# Power_Supply.net
KiCad netlist of a schematic drawn in EAGLE
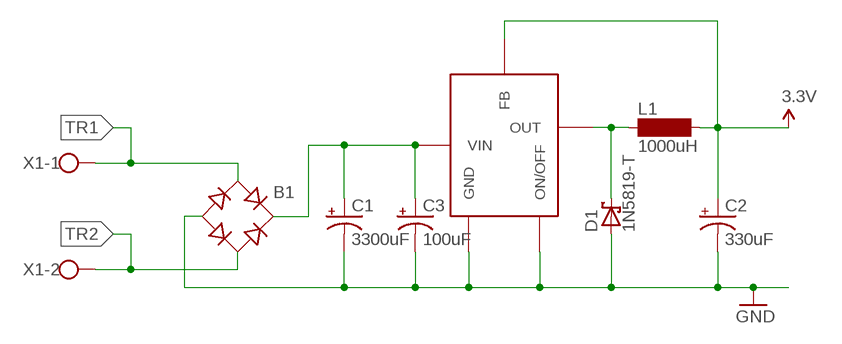
[diagram p0: schematic, sheet 1]

(export (version "E")
  (design (tool "Eeschema 10.0.6"))
  (components
    (comp (ref "B1")
      (value "DBDB101G")
      (footprint "eagle-import:DB")
      (libsource (lib "eagle-import") (part "DB?GDB101"))
    )
    (comp (ref "C1")
      (value "3300uF")
      (footprint "eagle-import:E7,5-18")
      (libsource (lib "eagle-import") (part "CPOL-USE7.5-18"))
    )
    (comp (ref "C2")
      (value "330uF")
      (footprint "eagle-import:E5-8,5")
      (libsource (lib "eagle-import") (part "CPOL-USE5-8.5"))
    )
    (comp (ref "C3")
      (value "100uF")
      (footprint "eagle-import:E5-8,5")
      (libsource (lib "eagle-import") (part "CPOL-USE5-8.5"))
    )
    (comp (ref "D1")
      (value "1N5819-T")
      (footprint "eagle-import:DO41-7.6")
      (libsource (lib "eagle-import") (part "1N5819-T"))
    )
    (comp (ref "L1")
      (value "1000uH")
      (footprint "eagle-import:BS11")
      (libsource (lib "eagle-import") (part "BS11"))
    )
    (comp (ref "U$1")
      (value "LM2575")
      (footprint "eagle-import:LINEAR-TECHNOLOGY_TO220-5")
      (libsource (lib "eagle-import") (part "LM2575"))
    )
    (comp (ref "X1")
      (value "W237-102")
      (footprint "eagle-import:W237-102")
      (fields (field (name "MPN") "237-102"))
      (libsource (lib "eagle-import") (part "W237-102"))
    )
  )
  (nets
    (net (code "1") (name "3.3V") (class "Default")
      (node (ref "C2") (pin "+") (pinfunction "+_+") (pintype "passive"))
      (node (ref "L1") (pin "2") (pinfunction "2_2") (pintype "passive"))
      (node (ref "U$1") (pin "FB") (pinfunction "FB_FB") (pintype "input"))
    )
    (net (code "2") (name "GND") (class "Default")
      (node (ref "B1") (pin "-") (pinfunction "-_-") (pintype "passive"))
      (node (ref "C1") (pin "-") (pinfunction "-_-") (pintype "passive"))
      (node (ref "C2") (pin "-") (pinfunction "-_-") (pintype "passive"))
      (node (ref "C3") (pin "-") (pinfunction "-_-") (pintype "passive"))
      (node (ref "D1") (pin "A") (pinfunction "A_A") (pintype "passive"))
      (node (ref "U$1") (pin "GND") (pinfunction "GND_GND") (pintype "power_in"))
      (node (ref "U$1") (pin "ON/OFF") (pinfunction "ON/OFF_ON/OFF") (pintype "input"))
    )
    (net (code "3") (name "Net-(B1-Pad+)") (class "Default")
      (node (ref "B1") (pin "+") (pinfunction "+_+") (pintype "passive"))
      (node (ref "C1") (pin "+") (pinfunction "+_+") (pintype "passive"))
      (node (ref "C3") (pin "+") (pinfunction "+_+") (pintype "passive"))
      (node (ref "U$1") (pin "VIN") (pinfunction "VIN_VIN") (pintype "power_in"))
    )
    (net (code "4") (name "Net-(D1-PadC)") (class "Default")
      (node (ref "D1") (pin "C") (pinfunction "C_C") (pintype "passive"))
      (node (ref "L1") (pin "1") (pinfunction "1_1") (pintype "passive"))
      (node (ref "U$1") (pin "OUT") (pinfunction "OUT_OUT") (pintype "power_in"))
    )
    (net (code "5") (name "TR1") (class "Default")
      (node (ref "B1") (pin "AC1") (pinfunction "AC1_AC1") (pintype "passive"))
      (node (ref "X1") (pin "1") (pinfunction "KL_1") (pintype "passive"))
    )
    (net (code "6") (name "TR2") (class "Default")
      (node (ref "B1") (pin "AC2") (pinfunction "AC2_AC2") (pintype "passive"))
      (node (ref "X1") (pin "2") (pinfunction "KL_2") (pintype "passive"))
    )
  )
)
